# Sheet1.net
KiCad netlist of a schematic drawn in Altium Designer
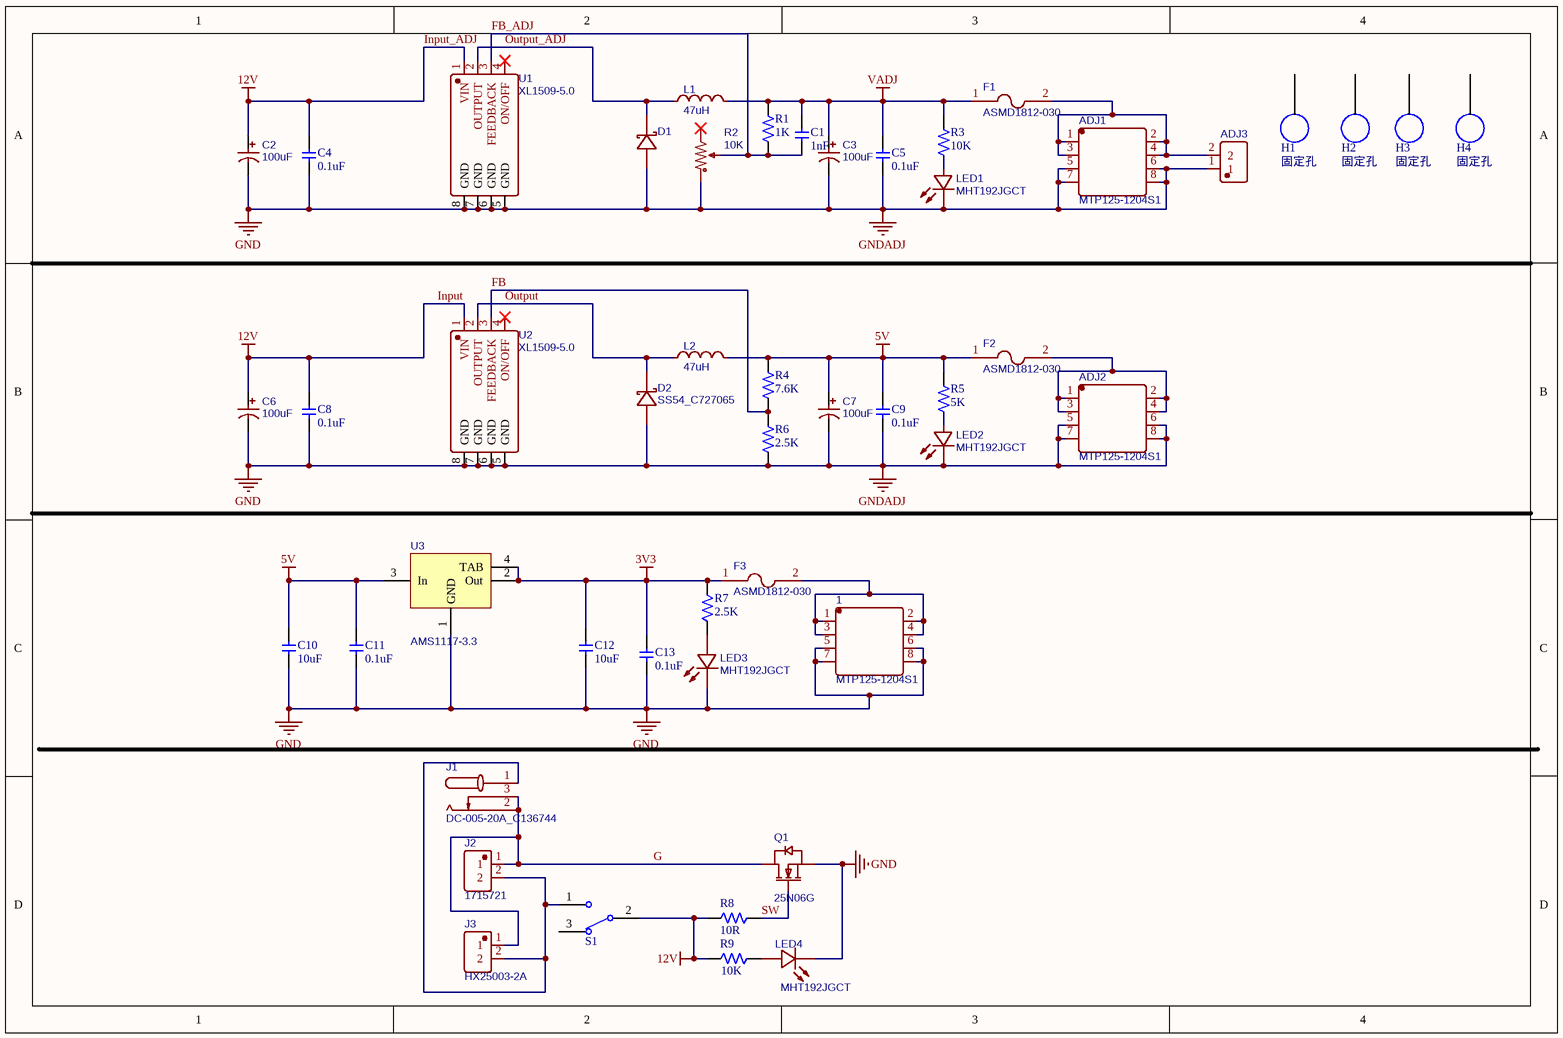
[diagram p0: Sheet1.SchDoc]

(export (version "E")
  (design (tool "Eeschema 10.0.6"))
  (components
    (comp (ref "1")
      (value "MTP125-1204S1")
      (footprint "HDR-TH_8P-P2.54-V-F-R2-C4-S2.54-1")
      (description "插针-弯")
      (fields (field (name "BOM_SUPPLIER PART") "C358693") (field (name "CONTRIBUTOR") "LCSC"))
      (libsource (lib "Schlib1") (part "MTP125-1204S1"))
    )
    (comp (ref "ADJ1")
      (value "MTP125-1204S1")
      (footprint "HDR-TH_8P-P2.54-V-F-R2-C4-S2.54-1")
      (description "插针-弯")
      (fields (field (name "BOM_SUPPLIER PART") "C358693") (field (name "CONTRIBUTOR") "LCSC"))
      (libsource (lib "Schlib1") (part "MTP125-1204S1"))
    )
    (comp (ref "ADJ2")
      (value "MTP125-1204S1")
      (footprint "HDR-TH_8P-P2.54-V-F-R2-C4-S2.54-1")
      (description "插针-弯")
      (fields (field (name "BOM_SUPPLIER PART") "C358693") (field (name "CONTRIBUTOR") "LCSC"))
      (libsource (lib "Schlib1") (part "MTP125-1204S1"))
    )
    (comp (ref "ADJ3")
      (value "1125-1102G0S116C001")
      (footprint "焊盘 2p")
      (description "毫伏电压表焊盘")
      (fields (field (name "BOM_SUPPLIER PART") "C920781") (field (name "CONTRIBUTOR") "LCSC"))
      (libsource (lib "Schlib1") (part "焊盘 2p"))
    )
    (comp (ref "C1") (value "1nF") (footprint "0603C") (libsource (lib "Schlib1") (part "C")))
    (comp (ref "C2")
      (value "100uF")
      (footprint "CAP-SMD_BD6.3-L6.6-W6.6-FD")
      (fields
        (field (name "BOM_MANUFACTURER PART") "CK1C101M-CRE54")
        (field (name "BOM_SUPPLIER PART") "C129250")
        (field (name "CONTRIBUTOR") "LCSC")
      )
      (libsource (lib "Schlib1") (part "100uF"))
    )
    (comp (ref "C3")
      (value "100uF")
      (footprint "CAP-SMD_BD6.3-L6.6-W6.6-FD")
      (fields
        (field (name "BOM_MANUFACTURER PART") "CK1C101M-CRE54")
        (field (name "BOM_SUPPLIER PART") "C129250")
        (field (name "CONTRIBUTOR") "LCSC")
      )
      (libsource (lib "Schlib1") (part "100uF"))
    )
    (comp (ref "C4") (value "0.1uF") (footprint "0603C") (libsource (lib "Schlib1") (part "C")))
    (comp (ref "C5") (value "0.1uF") (footprint "0603C") (libsource (lib "Schlib1") (part "C")))
    (comp (ref "C6")
      (value "100uF")
      (footprint "CAP-SMD_BD6.3-L6.6-W6.6-FD")
      (fields
        (field (name "BOM_MANUFACTURER PART") "CK1C101M-CRE54")
        (field (name "BOM_SUPPLIER PART") "C129250")
        (field (name "CONTRIBUTOR") "LCSC")
      )
      (libsource (lib "Schlib1") (part "100uF"))
    )
    (comp (ref "C7")
      (value "100uF")
      (footprint "CAP-SMD_BD6.3-L6.6-W6.6-FD")
      (fields
        (field (name "BOM_MANUFACTURER PART") "CK1C101M-CRE54")
        (field (name "BOM_SUPPLIER PART") "C129250")
        (field (name "CONTRIBUTOR") "LCSC")
      )
      (libsource (lib "Schlib1") (part "100uF"))
    )
    (comp (ref "C8") (value "0.1uF") (footprint "0603C") (libsource (lib "Schlib1") (part "C")))
    (comp (ref "C9") (value "0.1uF") (footprint "0603C") (libsource (lib "Schlib1") (part "C")))
    (comp (ref "C10") (value "10uF") (footprint "0603C") (libsource (lib "Schlib1") (part "C")))
    (comp (ref "C11") (value "0.1uF") (footprint "0603C") (libsource (lib "Schlib1") (part "C")))
    (comp (ref "C12") (value "10uF") (footprint "0603C") (libsource (lib "Schlib1") (part "C")))
    (comp (ref "C13") (value "0.1uF") (footprint "0603C") (libsource (lib "Schlib1") (part "C")))
    (comp (ref "D1")
      (value "SS54_C727065")
      (footprint "SMA_L4.3-W2.6-LS5.0-RD")
      (description "肖特基二极管")
      (fields
        (field (name "BOM_SUPPLIER PART") "C727065")
        (field (name "BOM_MANUFACTURER PART") "SS54")
        (field (name "CONTRIBUTOR") "LCSC")
      )
      (libsource (lib "Schlib1") (part "SS54_C727065"))
    )
    (comp (ref "D2")
      (value "SS54_C727065")
      (footprint "SMA_L4.3-W2.6-LS5.0-RD")
      (description "肖特基二极管")
      (fields
        (field (name "BOM_SUPPLIER PART") "C727065")
        (field (name "BOM_MANUFACTURER PART") "SS54")
        (field (name "CONTRIBUTOR") "LCSC")
      )
      (libsource (lib "Schlib1") (part "SS54_C727065"))
    )
    (comp (ref "F1")
      (value "ASMD1812-030")
      (footprint "F1812")
      (fields (field (name "BOM_SUPPLIER PART") "C135357") (field (name "CONTRIBUTOR") "LCSC"))
      (libsource (lib "Schlib1") (part "ASMD1812-030"))
    )
    (comp (ref "F2")
      (value "ASMD1812-030")
      (footprint "F1812")
      (fields (field (name "BOM_SUPPLIER PART") "C135357") (field (name "CONTRIBUTOR") "LCSC"))
      (libsource (lib "Schlib1") (part "ASMD1812-030"))
    )
    (comp (ref "F3")
      (value "ASMD1812-030")
      (footprint "F1812")
      (fields (field (name "BOM_SUPPLIER PART") "C135357") (field (name "CONTRIBUTOR") "LCSC"))
      (libsource (lib "Schlib1") (part "ASMD1812-030"))
    )
    (comp (ref "H1") (value "固定孔") (footprint "Gp-t") (libsource (lib "Schlib1") (part "固定孔")))
    (comp (ref "H2") (value "固定孔") (footprint "Gp-t") (libsource (lib "Schlib1") (part "固定孔")))
    (comp (ref "H3") (value "固定孔") (footprint "Gp-t") (libsource (lib "Schlib1") (part "固定孔")))
    (comp (ref "H4") (value "固定孔") (footprint "Gp-t") (libsource (lib "Schlib1") (part "固定孔")))
    (comp (ref "J1")
      (value "DC-005-20A_C136744")
      (footprint "DC-IN-TH_DC-005-20A")
      (fields
        (field (name "BOM_MANUFACTURER PART") "DC-005-20A")
        (field (name "BOM_SUPPLIER PART") "C136744")
        (field (name "CONTRIBUTOR") "LCSC")
      )
      (libsource (lib "Schlib1") (part "DC-005-20A_C136744"))
    )
    (comp (ref "J2")
      (value "1715721")
      (footprint "KF301-5.0-2P")
      (fields (field (name "BOM_SUPPLIER PART") "C480516") (field (name "CONTRIBUTOR") "LCSC"))
      (libsource (lib "Schlib1") (part "1715721"))
    )
    (comp (ref "J3")
      (value "HX25003-2A")
      (footprint "XH2.54-WI-2P")
      (fields (field (name "BOM_SUPPLIER PART") "C442299") (field (name "CONTRIBUTOR") "LCSC"))
      (libsource (lib "Schlib1") (part "HX25003-2A"))
    )
    (comp (ref "L1")
      (value "47uH")
      (footprint "IND-SMD_L7.1-W6.6")
      (fields
        (field (name "BOM_MANUFACTURER PART") "SMMS0650-330M")
        (field (name "BOM_SUPPLIER PART") "C149587")
      )
      (libsource (lib "Schlib1") (part "33uH"))
    )
    (comp (ref "L2")
      (value "47uH")
      (footprint "IND-SMD_L7.1-W6.6")
      (fields
        (field (name "BOM_MANUFACTURER PART") "SMMS0650-330M")
        (field (name "BOM_SUPPLIER PART") "C149587")
      )
      (libsource (lib "Schlib1") (part "33uH"))
    )
    (comp (ref "LED1")
      (value "MHT192JGCT")
      (footprint "LED0603-RD")
      (fields (field (name "BOM_SUPPLIER PART") "C473820") (field (name "CONTRIBUTOR") "LCSC"))
      (libsource (lib "Schlib1") (part "MHT192JGCT"))
    )
    (comp (ref "LED2")
      (value "MHT192JGCT")
      (footprint "LED0603-RD")
      (fields (field (name "BOM_SUPPLIER PART") "C473820") (field (name "CONTRIBUTOR") "LCSC"))
      (libsource (lib "Schlib1") (part "MHT192JGCT"))
    )
    (comp (ref "LED3")
      (value "MHT192JGCT")
      (footprint "LED0603-RD")
      (fields (field (name "BOM_SUPPLIER PART") "C473820") (field (name "CONTRIBUTOR") "LCSC"))
      (libsource (lib "Schlib1") (part "MHT192JGCT"))
    )
    (comp (ref "LED4")
      (value "MHT192JGCT")
      (footprint "LED0603-RD")
      (fields (field (name "BOM_SUPPLIER PART") "C473820") (field (name "CONTRIBUTOR") "LCSC"))
      (libsource (lib "Schlib1") (part "MHT192JGCT"))
    )
    (comp (ref "Q1")
      (value "25N06G")
      (footprint "TO-252-2_L6.6-W6.1-P4.57-LS9.9-BR-CW")
      (fields (field (name "BOM_SUPPLIER PART") "C432617") (field (name "CONTRIBUTOR") "LCSC"))
      (libsource (lib "Schlib1") (part "25N06G"))
    )
    (comp (ref "R1") (value "1K") (footprint "0603R") (libsource (lib "Schlib1") (part "R")))
    (comp (ref "R2")
      (value "10K")
      (footprint "RES-ADJ-TH_3P-L10.0-W10.0-P2.50-L")
      (description "电位器")
      (fields
        (field (name "BOM_SUPPLIER PART") "C118954")
        (field (name "BOM_MANUFACTURER PART") "3296W-1-103")
        (field (name "CONTRIBUTOR") "LCSC")
      )
      (libsource (lib "Schlib1") (part "10K"))
    )
    (comp (ref "R3") (value "10K") (footprint "0603R") (libsource (lib "Schlib1") (part "R")))
    (comp (ref "R4") (value "7.6K") (footprint "0603R") (libsource (lib "Schlib1") (part "R")))
    (comp (ref "R5") (value "5K") (footprint "0603R") (libsource (lib "Schlib1") (part "R")))
    (comp (ref "R6") (value "2.5K") (footprint "0603R") (libsource (lib "Schlib1") (part "R")))
    (comp (ref "R7") (value "2.5K") (footprint "0603R") (libsource (lib "Schlib1") (part "R")))
    (comp (ref "R8") (value "10R") (footprint "0603R") (libsource (lib "Schlib1") (part "R")))
    (comp (ref "R9") (value "10K") (footprint "0603R") (libsource (lib "Schlib1") (part "R")))
    (comp (ref "S1")
      (value "SW-SPDT")
      (footprint "钮子开关")
      (description "单刀双掷开关 3脚船型、钮子、拨动开关 SPDT Subminiature Toggle Switch")
      (fields (field (name "PUBLISHER") "Altium Limited"))
      (libsource (lib "Schlib1") (part "SW-SPDT"))
    )
    (comp (ref "U1")
      (value "XL1509-5.0")
      (footprint "SOIC-8_L5.0-W4.0-P1.27-LS6.0-BL")
      (description "开关电源3A")
      (fields (field (name "BOM_SUPPLIER PART") "C2681225") (field (name "CONTRIBUTOR") "LCSC"))
      (libsource (lib "Schlib1") (part "XL1509-5.0"))
    )
    (comp (ref "U2")
      (value "XL1509-5.0")
      (footprint "SOIC-8_L5.0-W4.0-P1.27-LS6.0-BL")
      (description "开关电源3A")
      (fields (field (name "BOM_SUPPLIER PART") "C2681225") (field (name "CONTRIBUTOR") "LCSC"))
      (libsource (lib "Schlib1") (part "XL1509-5.0"))
    )
    (comp (ref "U3")
      (value "AMS1117-3.3")
      (footprint "AMS1117")
      (description "3.3V稳压芯片")
      (fields (field (name "BOM_SUPPLIER PART") "C165482") (field (name "CONTRIBUTOR") "LCSC"))
      (libsource (lib "Schlib1") (part "AMS1117-3.3_C165482"))
    )
  )
  (nets
    (net (code "1") (name "/FB") (class "Default")
      (node (ref "R4") (pin "2") (pinfunction "2_2") (pintype "passive"))
      (node (ref "R6") (pin "1") (pinfunction "1_1") (pintype "passive"))
      (node (ref "U2") (pin "3") (pinfunction "FEEDBACK_3") (pintype "passive"))
    )
    (net (code "2") (name "/FB_ADJ") (class "Default")
      (node (ref "C1") (pin "1") (pinfunction "1_1") (pintype "passive"))
      (node (ref "R1") (pin "2") (pinfunction "2_2") (pintype "passive"))
      (node (ref "R2") (pin "2") (pinfunction "2_2") (pintype "passive"))
      (node (ref "U1") (pin "3") (pinfunction "FEEDBACK_3") (pintype "passive"))
    )
    (net (code "3") (name "/G") (class "Default")
      (node (ref "J1") (pin "2") (pinfunction "2_2") (pintype "passive"))
      (node (ref "J1") (pin "3") (pinfunction "3_3") (pintype "passive"))
      (node (ref "J2") (pin "1") (pinfunction "1_1") (pintype "passive"))
      (node (ref "J3") (pin "1") (pinfunction "1_1") (pintype "passive"))
      (node (ref "Q1") (pin "2") (pinfunction "D_2") (pintype "passive"))
    )
    (net (code "4") (name "/Output") (class "Default")
      (node (ref "D2") (pin "1") (pinfunction "1_1") (pintype "passive"))
      (node (ref "L2") (pin "1") (pinfunction "1_1") (pintype "passive"))
      (node (ref "U2") (pin "2") (pinfunction "OUTPUT_2") (pintype "passive"))
    )
    (net (code "5") (name "/Output_ADJ") (class "Default")
      (node (ref "D1") (pin "1") (pinfunction "1_1") (pintype "passive"))
      (node (ref "L1") (pin "1") (pinfunction "1_1") (pintype "passive"))
      (node (ref "U1") (pin "2") (pinfunction "OUTPUT_2") (pintype "passive"))
    )
    (net (code "6") (name "/SW") (class "Default")
      (node (ref "Q1") (pin "1") (pinfunction "G_1") (pintype "passive"))
      (node (ref "R8") (pin "1") (pinfunction "1_1") (pintype "passive"))
    )
    (net (code "7") (name "3V3") (class "Default")
      (node (ref "C12") (pin "2") (pinfunction "2_2") (pintype "passive"))
      (node (ref "C13") (pin "2") (pinfunction "2_2") (pintype "passive"))
      (node (ref "F3") (pin "1") (pinfunction "1_1") (pintype "passive"))
      (node (ref "R7") (pin "1") (pinfunction "1_1") (pintype "passive"))
      (node (ref "U3") (pin "2") (pinfunction "Out_2") (pintype "passive"))
      (node (ref "U3") (pin "4") (pinfunction "TAB_4") (pintype "passive"))
    )
    (net (code "8") (name "5V") (class "Default")
      (node (ref "C10") (pin "2") (pinfunction "2_2") (pintype "passive"))
      (node (ref "C11") (pin "2") (pinfunction "2_2") (pintype "passive"))
      (node (ref "C7") (pin "1") (pinfunction "1_1") (pintype "passive"))
      (node (ref "C9") (pin "2") (pinfunction "2_2") (pintype "passive"))
      (node (ref "F2") (pin "1") (pinfunction "1_1") (pintype "passive"))
      (node (ref "L2") (pin "2") (pinfunction "2_2") (pintype "passive"))
      (node (ref "R4") (pin "1") (pinfunction "1_1") (pintype "passive"))
      (node (ref "R5") (pin "1") (pinfunction "1_1") (pintype "passive"))
      (node (ref "U3") (pin "3") (pinfunction "In_3") (pintype "passive"))
    )
    (net (code "9") (name "12V") (class "Default")
      (node (ref "C2") (pin "1") (pinfunction "1_1") (pintype "passive"))
      (node (ref "C4") (pin "2") (pinfunction "2_2") (pintype "passive"))
      (node (ref "C6") (pin "1") (pinfunction "1_1") (pintype "passive"))
      (node (ref "C8") (pin "2") (pinfunction "2_2") (pintype "passive"))
      (node (ref "R8") (pin "2") (pinfunction "2_2") (pintype "passive"))
      (node (ref "R9") (pin "2") (pinfunction "2_2") (pintype "passive"))
      (node (ref "S1") (pin "2") (pintype "passive"))
      (node (ref "U1") (pin "1") (pinfunction "VIN_1") (pintype "passive"))
      (node (ref "U2") (pin "1") (pinfunction "VIN_1") (pintype "passive"))
    )
    (net (code "10") (name "GND") (class "Default")
      (node (ref "1") (pin "5") (pinfunction "5_5") (pintype "passive"))
      (node (ref "1") (pin "6") (pinfunction "6_6") (pintype "passive"))
      (node (ref "1") (pin "7") (pinfunction "7_7") (pintype "passive"))
      (node (ref "1") (pin "8") (pinfunction "8_8") (pintype "passive"))
      (node (ref "ADJ1") (pin "5") (pinfunction "5_5") (pintype "passive"))
      (node (ref "ADJ1") (pin "6") (pinfunction "6_6") (pintype "passive"))
      (node (ref "ADJ1") (pin "7") (pinfunction "7_7") (pintype "passive"))
      (node (ref "ADJ1") (pin "8") (pinfunction "8_8") (pintype "passive"))
      (node (ref "ADJ2") (pin "5") (pinfunction "5_5") (pintype "passive"))
      (node (ref "ADJ2") (pin "6") (pinfunction "6_6") (pintype "passive"))
      (node (ref "ADJ2") (pin "7") (pinfunction "7_7") (pintype "passive"))
      (node (ref "ADJ2") (pin "8") (pinfunction "8_8") (pintype "passive"))
      (node (ref "ADJ3") (pin "1") (pinfunction "1_1") (pintype "passive"))
      (node (ref "C10") (pin "1") (pinfunction "1_1") (pintype "passive"))
      (node (ref "C11") (pin "1") (pinfunction "1_1") (pintype "passive"))
      (node (ref "C12") (pin "1") (pinfunction "1_1") (pintype "passive"))
      (node (ref "C13") (pin "1") (pinfunction "1_1") (pintype "passive"))
      (node (ref "C2") (pin "2") (pinfunction "2_2") (pintype "passive"))
      (node (ref "C3") (pin "2") (pinfunction "2_2") (pintype "passive"))
      (node (ref "C4") (pin "1") (pinfunction "1_1") (pintype "passive"))
      (node (ref "C5") (pin "1") (pinfunction "1_1") (pintype "passive"))
      (node (ref "C6") (pin "2") (pinfunction "2_2") (pintype "passive"))
      (node (ref "C7") (pin "2") (pinfunction "2_2") (pintype "passive"))
      (node (ref "C8") (pin "1") (pinfunction "1_1") (pintype "passive"))
      (node (ref "C9") (pin "1") (pinfunction "1_1") (pintype "passive"))
      (node (ref "D1") (pin "2") (pinfunction "2_2") (pintype "passive"))
      (node (ref "D2") (pin "2") (pinfunction "2_2") (pintype "passive"))
      (node (ref "LED1") (pin "1") (pinfunction "-_1") (pintype "passive"))
      (node (ref "LED2") (pin "1") (pinfunction "-_1") (pintype "passive"))
      (node (ref "LED3") (pin "1") (pinfunction "-_1") (pintype "passive"))
      (node (ref "LED4") (pin "1") (pinfunction "-_1") (pintype "passive"))
      (node (ref "Q1") (pin "3") (pinfunction "S_3") (pintype "passive"))
      (node (ref "R2") (pin "1") (pinfunction "1_1") (pintype "passive"))
      (node (ref "R6") (pin "2") (pinfunction "2_2") (pintype "passive"))
      (node (ref "U1") (pin "5") (pinfunction "GND_5") (pintype "passive"))
      (node (ref "U1") (pin "6") (pinfunction "GND_6") (pintype "passive"))
      (node (ref "U1") (pin "7") (pinfunction "GND_7") (pintype "passive"))
      (node (ref "U1") (pin "8") (pinfunction "GND_8") (pintype "passive"))
      (node (ref "U2") (pin "5") (pinfunction "GND_5") (pintype "passive"))
      (node (ref "U2") (pin "6") (pinfunction "GND_6") (pintype "passive"))
      (node (ref "U2") (pin "7") (pinfunction "GND_7") (pintype "passive"))
      (node (ref "U2") (pin "8") (pinfunction "GND_8") (pintype "passive"))
      (node (ref "U3") (pin "1") (pinfunction "GND_1") (pintype "passive"))
    )
    (net (code "11") (name "Net-(1-Pad1)") (class "Default")
      (node (ref "1") (pin "1") (pinfunction "1_1") (pintype "passive"))
      (node (ref "1") (pin "2") (pinfunction "2_2") (pintype "passive"))
      (node (ref "1") (pin "3") (pinfunction "3_3") (pintype "passive"))
      (node (ref "1") (pin "4") (pinfunction "4_4") (pintype "passive"))
      (node (ref "F3") (pin "2") (pinfunction "2_2") (pintype "passive"))
    )
    (net (code "12") (name "Net-(ADJ1-Pad1)") (class "Default")
      (node (ref "ADJ1") (pin "1") (pinfunction "1_1") (pintype "passive"))
      (node (ref "ADJ1") (pin "2") (pinfunction "2_2") (pintype "passive"))
      (node (ref "ADJ1") (pin "3") (pinfunction "3_3") (pintype "passive"))
      (node (ref "ADJ1") (pin "4") (pinfunction "4_4") (pintype "passive"))
      (node (ref "ADJ3") (pin "2") (pinfunction "2_2") (pintype "passive"))
      (node (ref "F1") (pin "2") (pinfunction "2_2") (pintype "passive"))
    )
    (net (code "13") (name "Net-(ADJ2-Pad1)") (class "Default")
      (node (ref "ADJ2") (pin "1") (pinfunction "1_1") (pintype "passive"))
      (node (ref "ADJ2") (pin "2") (pinfunction "2_2") (pintype "passive"))
      (node (ref "ADJ2") (pin "3") (pinfunction "3_3") (pintype "passive"))
      (node (ref "ADJ2") (pin "4") (pinfunction "4_4") (pintype "passive"))
      (node (ref "F2") (pin "2") (pinfunction "2_2") (pintype "passive"))
    )
    (net (code "14") (name "Net-(J1-Pad1)") (class "Default")
      (node (ref "J1") (pin "1") (pinfunction "1_1") (pintype "passive"))
      (node (ref "J2") (pin "2") (pinfunction "2_2") (pintype "passive"))
      (node (ref "J3") (pin "2") (pinfunction "2_2") (pintype "passive"))
      (node (ref "S1") (pin "1") (pintype "passive"))
    )
    (net (code "15") (name "Net-(LED1-+)") (class "Default")
      (node (ref "LED1") (pin "2") (pinfunction "+_2") (pintype "passive"))
      (node (ref "R3") (pin "2") (pinfunction "2_2") (pintype "passive"))
    )
    (net (code "16") (name "Net-(LED2-+)") (class "Default")
      (node (ref "LED2") (pin "2") (pinfunction "+_2") (pintype "passive"))
      (node (ref "R5") (pin "2") (pinfunction "2_2") (pintype "passive"))
    )
    (net (code "17") (name "Net-(LED3-+)") (class "Default")
      (node (ref "LED3") (pin "2") (pinfunction "+_2") (pintype "passive"))
      (node (ref "R7") (pin "2") (pinfunction "2_2") (pintype "passive"))
    )
    (net (code "18") (name "Net-(LED4-+)") (class "Default")
      (node (ref "LED4") (pin "2") (pinfunction "+_2") (pintype "passive"))
      (node (ref "R9") (pin "1") (pinfunction "1_1") (pintype "passive"))
    )
    (net (code "19") (name "VADJ") (class "Default")
      (node (ref "C1") (pin "2") (pinfunction "2_2") (pintype "passive"))
      (node (ref "C3") (pin "1") (pinfunction "1_1") (pintype "passive"))
      (node (ref "C5") (pin "2") (pinfunction "2_2") (pintype "passive"))
      (node (ref "F1") (pin "1") (pinfunction "1_1") (pintype "passive"))
      (node (ref "L1") (pin "2") (pinfunction "2_2") (pintype "passive"))
      (node (ref "R1") (pin "1") (pinfunction "1_1") (pintype "passive"))
      (node (ref "R3") (pin "1") (pinfunction "1_1") (pintype "passive"))
    )
    (net (code "20") (name "unconnected-(H1-Pad1)") (class "Default")
      (node (ref "H1") (pin "1") (pinfunction "1_1") (pintype "passive"))
    )
    (net (code "21") (name "unconnected-(H2-Pad1)") (class "Default")
      (node (ref "H2") (pin "1") (pinfunction "1_1") (pintype "passive"))
    )
    (net (code "22") (name "unconnected-(H3-Pad1)") (class "Default")
      (node (ref "H3") (pin "1") (pinfunction "1_1") (pintype "passive"))
    )
    (net (code "23") (name "unconnected-(H4-Pad1)") (class "Default")
      (node (ref "H4") (pin "1") (pinfunction "1_1") (pintype "passive"))
    )
    (net (code "24") (name "unconnected-(R2-Pad3)") (class "Default")
      (node (ref "R2") (pin "3") (pinfunction "3_3") (pintype "passive+no_connect"))
    )
    (net (code "25") (name "unconnected-(S1-Pad3)") (class "Default")
      (node (ref "S1") (pin "3") (pintype "passive"))
    )
    (net (code "26") (name "unconnected-(U1-ON{slash}OFF-Pad4)") (class "Default")
      (node (ref "U1") (pin "4") (pinfunction "ON/OFF_4") (pintype "passive+no_connect"))
    )
    (net (code "27") (name "unconnected-(U2-ON{slash}OFF-Pad4)") (class "Default")
      (node (ref "U2") (pin "4") (pinfunction "ON/OFF_4") (pintype "passive+no_connect"))
    )
  )
)
